# ps.net
KiCad netlist of a schematic drawn in Altium Designer
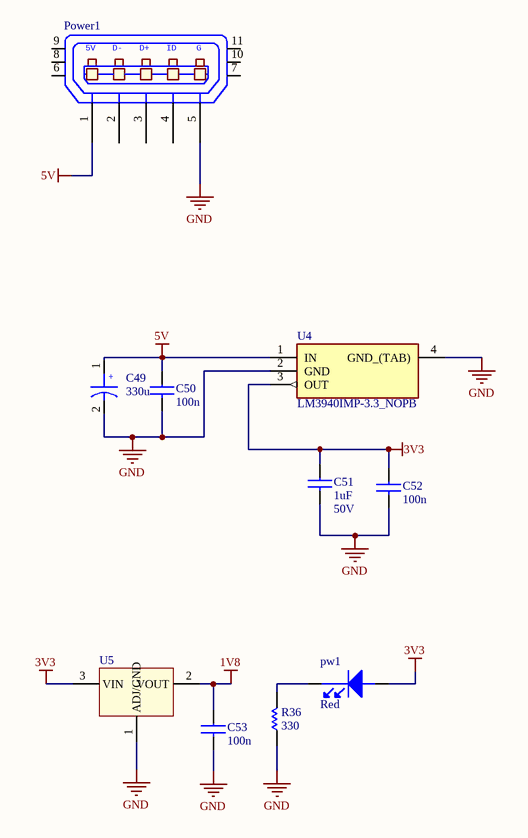
[diagram p0: ps.SchDoc]

(export (version "E")
  (design (tool "Eeschema 10.0.6"))
  (components
    (comp (ref "C49")
      (value "330u")
      (footprint "C2917")
      (description "CAP TANT 330UF 10V 10% 2917")
      (fields
        (field (name "MANUFACTURER") "Kemet")
        (field (name "MANUFACTURER PART NUMBER") "T495D337K010ATE150")
        (field (name ".CREATOR") "MM")
        (field (name ".CHECKED PCB") "MM")
        (field (name ".CHECKED SCH") "RF, used by MM")
      )
      (libsource (lib "iMX6_Rex_Development_Baseboard_V1I1") (part "T495D337K010ATE150"))
    )
    (comp (ref "C50")
      (value "100n")
      (footprint "C0402")
      (description "CAP CER .10UF 50V X5R 10% 0402")
      (fields
        (field (name "MANUFACTURER") "TDK Corporation")
        (field (name "MANUFACTURER PART NUMBER") "C1005X5R1H104K")
      )
      (libsource (lib "iMX6_Rex_Development_Baseboard_V1I1") (part "C1005X5R1H104K"))
    )
    (comp (ref "C51")
      (value "1uF")
      (footprint "C0805")
      (description "CAP CER 1UF 50V X7R 0805")
      (fields
        (field (name "MANUFACTURER") "Murata Electronics North America")
        (field (name "MANUFACTURER PART NUMBER") "GRM21BR71H105KA12L")
        (field (name "VOLTAGE - RATED") "50V")
      )
      (libsource (lib "iMX6_Rex_Development_Baseboard_V1I1") (part "GRM21BR71H105KA12L"))
    )
    (comp (ref "C52")
      (value "100n")
      (footprint "C0402")
      (description "CAP CER .10UF 50V X5R 10% 0402")
      (fields
        (field (name "MANUFACTURER") "TDK Corporation")
        (field (name "MANUFACTURER PART NUMBER") "C1005X5R1H104K")
      )
      (libsource (lib "iMX6_Rex_Development_Baseboard_V1I1") (part "C1005X5R1H104K"))
    )
    (comp (ref "C53")
      (value "100n")
      (footprint "C0402")
      (description "CAP CER .10UF 50V X5R 10% 0402")
      (fields
        (field (name "MANUFACTURER") "TDK Corporation")
        (field (name "MANUFACTURER PART NUMBER") "C1005X5R1H104K")
      )
      (libsource (lib "iMX6_Rex_Development_Baseboard_V1I1") (part "C1005X5R1H104K"))
    )
    (comp (ref "Power1")
      (value "USB MICRO AB")
      (footprint "USB_Micro_AB")
      (description "CONN RCPT MICRO USB AB R/A SMD")
      (fields
        (field (name "MANUFACTURER") "Molex Inc")
        (field (name "MANUFACTURER PART NUMBER") "0475890001")
        (field (name ".CREATOR") "MM")
        (field (name ".CHECKED PCB") "MM")
        (field (name ".CHECKED SCH") "MM")
      )
      (libsource (lib "iMX6_Rex_Development_Baseboard_V1I1") (part "0475890001"))
    )
    (comp (ref "pw1")
      (value "Red")
      (footprint "LED_0603")
      (description "LED SMARTLED RED 630NM 0603 SMD")
      (fields
        (field (name "MANUFACTURER") "OSRAM Opto Semiconductors Inc")
        (field (name "MANUFACTURER PART NUMBER") "LS L29K-H1J2-1-Z")
        (field (name ".CHECKED PCB") "RF")
        (field (name ".CHECKED SCH") "RF")
      )
      (libsource (lib "iMX6_Rex_Development_Baseboard_V1I1") (part "LS L29K-H1J2-1-Z"))
    )
    (comp (ref "R36") (value "330") (footprint "RES 1206") (libsource (lib "L1") (part "RESISTOR")))
    (comp (ref "U4")
      (value "LM3940IMP-3.3_NOPB")
      (footprint "SamacSys:SOT230P700X180-4N")
      (description "Integrated Circuit")
      (fields
        (field (name "MANUFACTURER_PART_NUMBER") "LM3940IMP-3.3/NOPB")
        (field (name "MOUSER PART NUMBER") "926-LM3940IMP3.3NOPB")
      )
      (libsource (lib "*") (part "LM3940IMP-3.3_NOPB"))
    )
    (comp (ref "U5")
      (value "AMS1117")
      (footprint "AMS1117")
      (description "SOT-223-3 3V3 Regulator")
      (libsource (lib "L1") (part "AMS1117"))
    )
  )
  (nets
    (net (code "1") (name "1V8") (class "Default")
      (node (ref "C53") (pin "1") (pinfunction "1_1") (pintype "passive"))
      (node (ref "U5") (pin "2") (pinfunction "VOUT_2") (pintype "power_in"))
    )
    (net (code "2") (name "3V3") (class "Default")
      (node (ref "C51") (pin "1") (pinfunction "1_1") (pintype "passive"))
      (node (ref "C52") (pin "1") (pinfunction "1_1") (pintype "passive"))
      (node (ref "U4") (pin "3") (pinfunction "OUT_3") (pintype "output"))
      (node (ref "U5") (pin "3") (pinfunction "VIN_3") (pintype "power_in"))
      (node (ref "pw1") (pin "2") (pinfunction "ANODE_2") (pintype "passive"))
    )
    (net (code "3") (name "5V") (class "Default")
      (node (ref "C49") (pin "1") (pinfunction "1_1") (pintype "passive"))
      (node (ref "C50") (pin "1") (pinfunction "1_1") (pintype "passive"))
      (node (ref "Power1") (pin "1") (pinfunction "P1_1") (pintype "passive"))
      (node (ref "U4") (pin "1") (pinfunction "IN_1") (pintype "power_in"))
    )
    (net (code "4") (name "GND") (class "Default")
      (node (ref "C49") (pin "2") (pinfunction "2_2") (pintype "passive"))
      (node (ref "C50") (pin "2") (pinfunction "2_2") (pintype "passive"))
      (node (ref "C51") (pin "2") (pinfunction "2_2") (pintype "passive"))
      (node (ref "C52") (pin "2") (pinfunction "2_2") (pintype "passive"))
      (node (ref "C53") (pin "2") (pinfunction "2_2") (pintype "passive"))
      (node (ref "Power1") (pin "5") (pinfunction "P5_5") (pintype "passive"))
      (node (ref "R36") (pin "1") (pinfunction "1_1") (pintype "power_in"))
      (node (ref "U4") (pin "2") (pinfunction "GND_2") (pintype "power_in"))
      (node (ref "U4") (pin "4") (pinfunction "GND_(TAB)_4") (pintype "power_in"))
      (node (ref "U5") (pin "1") (pinfunction "ADJ/GND_1") (pintype "power_in"))
    )
    (net (code "5") (name "Net-(pw1-cathode)") (class "Default")
      (node (ref "R36") (pin "2") (pinfunction "2_2") (pintype "power_in"))
      (node (ref "pw1") (pin "1") (pinfunction "cathode_1") (pintype "passive"))
    )
    (net (code "6") (name "unconnected-(Power1-P2-Pad2)") (class "Default")
      (node (ref "Power1") (pin "2") (pinfunction "P2_2") (pintype "passive"))
    )
    (net (code "7") (name "unconnected-(Power1-P3-Pad3)") (class "Default")
      (node (ref "Power1") (pin "3") (pinfunction "P3_3") (pintype "passive"))
    )
    (net (code "8") (name "unconnected-(Power1-P4-Pad4)") (class "Default")
      (node (ref "Power1") (pin "4") (pinfunction "P4_4") (pintype "passive"))
    )
    (net (code "9") (name "unconnected-(Power1-Pad6)") (class "Default")
      (node (ref "Power1") (pin "6") (pinfunction "6_6") (pintype "passive"))
    )
    (net (code "10") (name "unconnected-(Power1-Pad7)") (class "Default")
      (node (ref "Power1") (pin "7") (pinfunction "7_7") (pintype "passive"))
    )
    (net (code "11") (name "unconnected-(Power1-Pad8)") (class "Default")
      (node (ref "Power1") (pin "8") (pinfunction "8_8") (pintype "passive"))
    )
    (net (code "12") (name "unconnected-(Power1-Pad9)") (class "Default")
      (node (ref "Power1") (pin "9") (pinfunction "9_9") (pintype "passive"))
    )
    (net (code "13") (name "unconnected-(Power1-Pad10)") (class "Default")
      (node (ref "Power1") (pin "10") (pinfunction "10_10") (pintype "passive"))
    )
    (net (code "14") (name "unconnected-(Power1-Pad11)") (class "Default")
      (node (ref "Power1") (pin "11") (pinfunction "11_11") (pintype "passive"))
    )
  )
)
